# BTN7960_DRIVER_SCH.net
KiCad netlist of a schematic drawn in Altium Designer
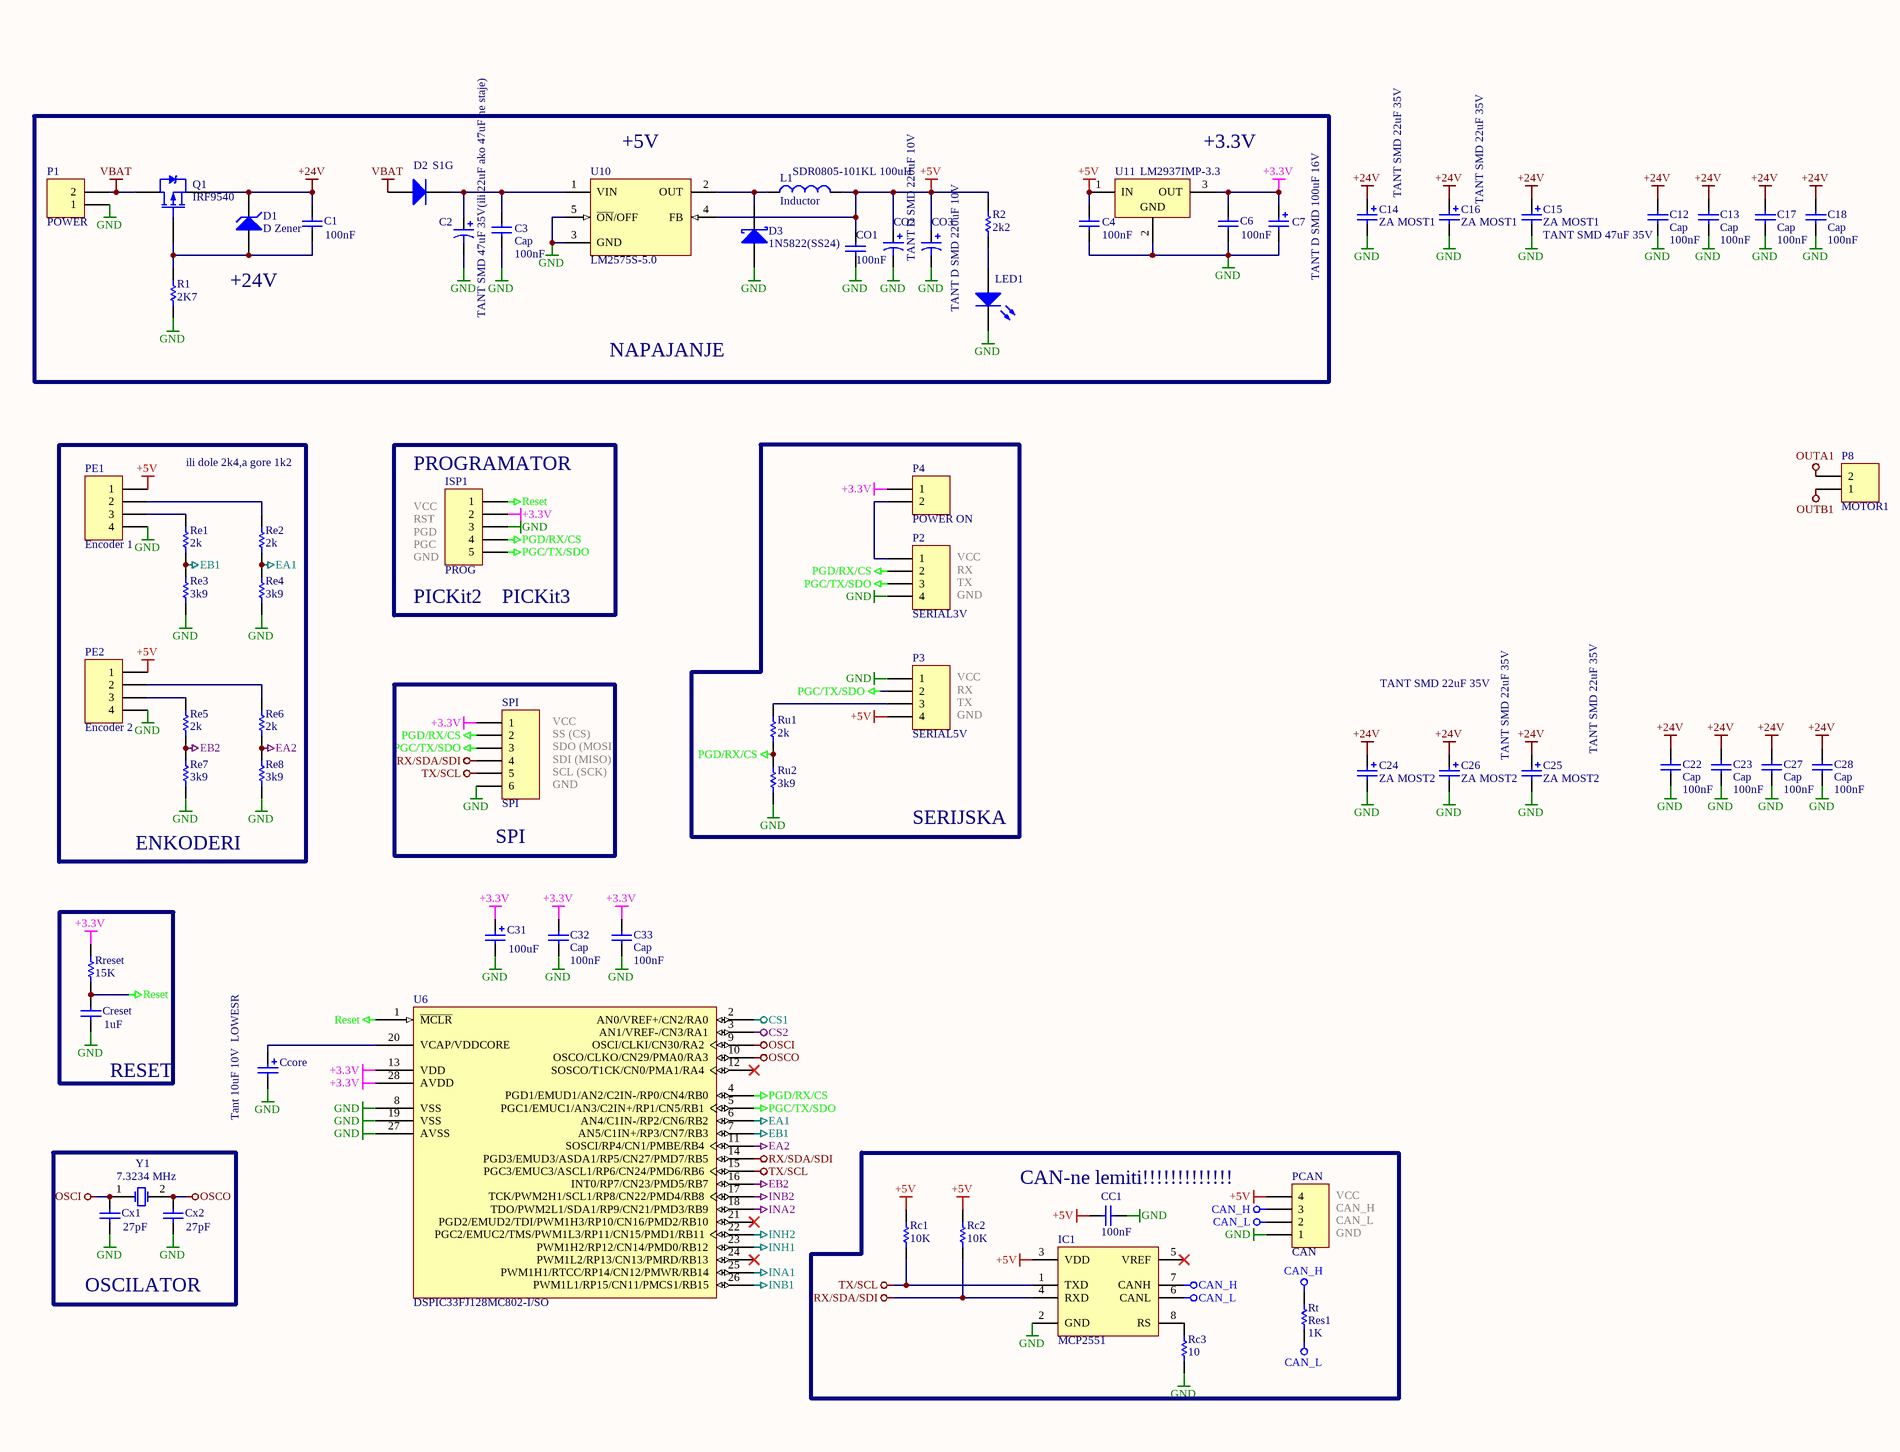
[diagram p0: BTN7960_DRIVER_SCH.SchDoc, left]
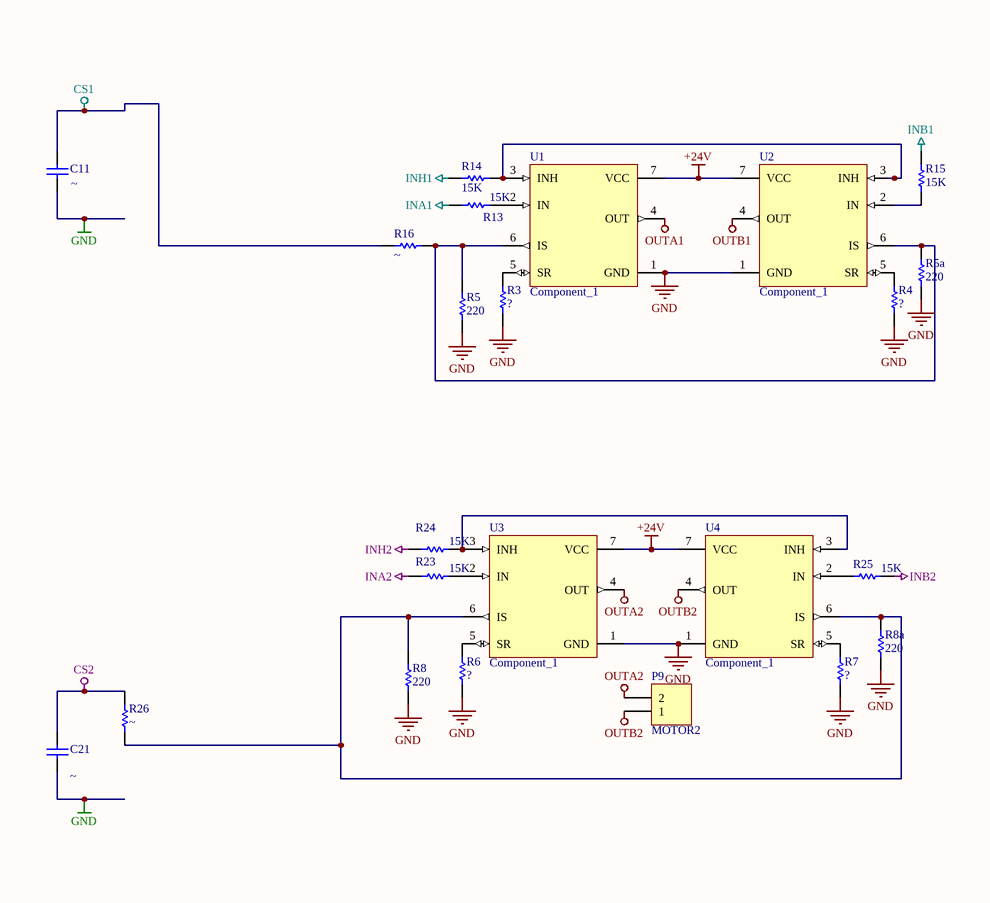
[diagram p1: BTN7960_DRIVER_SCH.SchDoc, right]

(export (version "E")
  (design (tool "Eeschema 10.0.6"))
  (components
    (comp (ref "C1")
      (value "100nF")
      (footprint "1206")
      (description "Capacitor")
      (fields (field (name "Comment") "Cap") (field (name "PUBLISHER") "Altium Limited"))
      (libsource (lib "SCH_LIB") (part "Cap"))
    )
    (comp (ref "C2")
      (value "TANT SMD 47uF 35V(ili 22uF ako 47uF ne staje)")
      (footprint "TC7343-2917")
      (description "Polarized Capacitor (Radial)")
      (fields (field (name "Comment") "Cap Pol1") (field (name "PUBLISHER") "Altium Limited"))
      (libsource (lib "Miscellaneous Devices") (part "Cap Pol1"))
    )
    (comp (ref "C3")
      (value "Cap")
      (footprint "1206")
      (description "Capacitor")
      (fields (field (name "ALTIUM_VALUE") "100nF") (field (name "PUBLISHER") "Altium Limited"))
      (libsource (lib "Miscellaneous Devices") (part "Cap"))
    )
    (comp (ref "C4")
      (value "100nF")
      (footprint "1206")
      (description "Capacitor")
      (fields (field (name "Comment") "Cap") (field (name "PUBLISHER") "Altium Limited"))
      (libsource (lib "SCH_LIB") (part "Cap"))
    )
    (comp (ref "C6")
      (value "100nF")
      (footprint "1206")
      (description "Capacitor")
      (fields (field (name "Comment") "Cap") (field (name "PUBLISHER") "Altium Limited"))
      (libsource (lib "SCH_LIB") (part "Cap"))
    )
    (comp (ref "C7")
      (value "TANT D SMD 100uF 16V")
      (footprint "TC7343-2917")
      (description "Polarized Capacitor (Radial)")
      (fields (field (name "Comment") "ECAP") (field (name "PUBLISHER") "Altium Limited"))
      (libsource (lib "SCH_LIB") (part "Cap Pol1"))
    )
    (comp (ref "C11")
      (value "~")
      (footprint "1206")
      (description "Capacitor")
      (fields (field (name "Comment") "Cap") (field (name "PUBLISHER") "Altium Limited"))
      (libsource (lib "SCH_LIB") (part "Cap"))
    )
    (comp (ref "C12")
      (value "Cap")
      (footprint "1206")
      (description "Capacitor")
      (fields (field (name "ALTIUM_VALUE") "100nF") (field (name "PUBLISHER") "Altium Limited"))
      (libsource (lib "SCH_LIB") (part "Cap"))
    )
    (comp (ref "C13")
      (value "Cap")
      (footprint "1206")
      (description "Capacitor")
      (fields (field (name "ALTIUM_VALUE") "100nF") (field (name "PUBLISHER") "Altium Limited"))
      (libsource (lib "SCH_LIB") (part "Cap"))
    )
    (comp (ref "C14")
      (value "ZA MOST1")
      (footprint "VNH_DRAJVER_PCB_v2.1:TC7343-2917")
      (description "Polarized Capacitor (Radial)")
      (fields (field (name "ALTIUM_VALUE") "TANT SMD 22uF 35V") (field (name "PUBLISHER") "Altium Limited"))
      (libsource (lib "SCH_LIB") (part "Cap Pol1"))
    )
    (comp (ref "C15")
      (value "ZA MOST1")
      (footprint "TC7343-2917")
      (description "Polarized Capacitor (Radial)")
      (fields (field (name "ALTIUM_VALUE") "TANT SMD 47uF 35V") (field (name "PUBLISHER") "Altium Limited"))
      (libsource (lib "SCH_LIB") (part "Cap Pol1"))
    )
    (comp (ref "C16")
      (value "ZA MOST1")
      (footprint "VNH_DRAJVER_PCB_v2.1:TC7343-2917")
      (description "Polarized Capacitor (Radial)")
      (fields (field (name "ALTIUM_VALUE") "TANT SMD 22uF 35V") (field (name "PUBLISHER") "Altium Limited"))
      (libsource (lib "SCH_LIB") (part "Cap Pol1"))
    )
    (comp (ref "C17")
      (value "Cap")
      (footprint "1206")
      (description "Capacitor")
      (fields (field (name "ALTIUM_VALUE") "100nF") (field (name "PUBLISHER") "Altium Limited"))
      (libsource (lib "SCH_LIB") (part "Cap"))
    )
    (comp (ref "C18")
      (value "Cap")
      (footprint "1206")
      (description "Capacitor")
      (fields (field (name "ALTIUM_VALUE") "100nF") (field (name "PUBLISHER") "Altium Limited"))
      (libsource (lib "SCH_LIB") (part "Cap"))
    )
    (comp (ref "C21")
      (value "~")
      (footprint "1206")
      (description "Capacitor")
      (fields (field (name "Comment") "Cap") (field (name "PUBLISHER") "Altium Limited"))
      (libsource (lib "SCH_LIB") (part "Cap"))
    )
    (comp (ref "C22")
      (value "Cap")
      (footprint "1206")
      (description "Capacitor")
      (fields (field (name "ALTIUM_VALUE") "100nF") (field (name "PUBLISHER") "Altium Limited"))
      (libsource (lib "SCH_LIB") (part "Cap"))
    )
    (comp (ref "C23")
      (value "Cap")
      (footprint "1206")
      (description "Capacitor")
      (fields (field (name "ALTIUM_VALUE") "100nF") (field (name "PUBLISHER") "Altium Limited"))
      (libsource (lib "SCH_LIB") (part "Cap"))
    )
    (comp (ref "C24")
      (value "ZA MOST2")
      (footprint "TC7343-2917")
      (description "Polarized Capacitor (Radial)")
      (fields (field (name "ALTIUM_VALUE") "TANT SMD 22uF 35V") (field (name "PUBLISHER") "Altium Limited"))
      (libsource (lib "SCH_LIB") (part "Cap Pol1"))
    )
    (comp (ref "C25")
      (value "ZA MOST2")
      (footprint "TC7343-2917")
      (description "Polarized Capacitor (Radial)")
      (fields (field (name "ALTIUM_VALUE") "TANT SMD 22uF 35V") (field (name "PUBLISHER") "Altium Limited"))
      (libsource (lib "SCH_LIB") (part "Cap Pol1"))
    )
    (comp (ref "C26")
      (value "ZA MOST2")
      (footprint "TC7343-2917")
      (description "Polarized Capacitor (Radial)")
      (fields (field (name "ALTIUM_VALUE") "TANT SMD 22uF 35V") (field (name "PUBLISHER") "Altium Limited"))
      (libsource (lib "SCH_LIB") (part "Cap Pol1"))
    )
    (comp (ref "C27")
      (value "Cap")
      (footprint "1206")
      (description "Capacitor")
      (fields (field (name "ALTIUM_VALUE") "100nF") (field (name "PUBLISHER") "Altium Limited"))
      (libsource (lib "SCH_LIB") (part "Cap"))
    )
    (comp (ref "C28")
      (value "Cap")
      (footprint "1206")
      (description "Capacitor")
      (fields (field (name "ALTIUM_VALUE") "100nF") (field (name "PUBLISHER") "Altium Limited"))
      (libsource (lib "SCH_LIB") (part "Cap"))
    )
    (comp (ref "C31")
      (value "100uF")
      (footprint "TC7343-2917")
      (description "Polarized Capacitor (Radial)")
      (fields (field (name "Comment") "ZA MOST1") (field (name "PUBLISHER") "Altium Limited"))
      (libsource (lib "SCH_LIB") (part "Cap Pol1"))
    )
    (comp (ref "C32")
      (value "Cap")
      (footprint "1206")
      (description "Capacitor")
      (fields (field (name "ALTIUM_VALUE") "100nF") (field (name "PUBLISHER") "Altium Limited"))
      (libsource (lib "SCH_LIB") (part "Cap"))
    )
    (comp (ref "C33")
      (value "Cap")
      (footprint "1206")
      (description "Capacitor")
      (fields (field (name "ALTIUM_VALUE") "100nF") (field (name "PUBLISHER") "Altium Limited"))
      (libsource (lib "SCH_LIB") (part "Cap"))
    )
    (comp (ref "CC1")
      (value "100nF")
      (footprint "1206")
      (description "Capacitor")
      (fields (field (name "Comment") "Cap") (field (name "PUBLISHER") "Altium Limited"))
      (libsource (lib "SCH_LIB") (part "Cap"))
    )
    (comp (ref "Ccore")
      (value "Tant 10uF 10V  LOWESR")
      (footprint "VNH_DRAJVER_PCB_v2.1:TC7343-2917")
      (description "Polarized Capacitor (Radial)")
      (fields (field (name "Comment") "ECAP") (field (name "PUBLISHER") "Altium Limited"))
      (libsource (lib "SCH_LIB") (part "Cap Pol1"))
    )
    (comp (ref "CO1")
      (value "100nF")
      (footprint "1206")
      (description "Capacitor")
      (fields (field (name "Comment") "Cap") (field (name "PUBLISHER") "Altium Limited"))
      (libsource (lib "Miscellaneous Devices") (part "Cap"))
    )
    (comp (ref "CO2")
      (value "TANT D SMD 220uF 10V")
      (footprint "TC7343-2917")
      (description "Polarized Capacitor (Radial)")
      (fields (field (name "Comment") "Cap Pol1") (field (name "PUBLISHER") "Altium Limited"))
      (libsource (lib "Miscellaneous Devices") (part "Cap Pol1"))
    )
    (comp (ref "CO3")
      (value "TANT D SMD 220uF 10V")
      (footprint "TC7343-2917")
      (description "Polarized Capacitor (Radial)")
      (fields (field (name "Comment") "Cap Pol1") (field (name "PUBLISHER") "Altium Limited"))
      (libsource (lib "Miscellaneous Devices") (part "Cap Pol1"))
    )
    (comp (ref "Creset")
      (value "1uF")
      (footprint "1206")
      (description "Capacitor")
      (fields (field (name "Comment") "Cap") (field (name "PUBLISHER") "Altium Limited"))
      (libsource (lib "SCH_LIB") (part "Cap"))
    )
    (comp (ref "Cx1")
      (value "27pF")
      (footprint "1206")
      (description "Capacitor")
      (fields (field (name "Comment") "Cap") (field (name "PUBLISHER") "Altium Limited"))
      (libsource (lib "SCH_LIB") (part "Cap"))
    )
    (comp (ref "Cx2")
      (value "27pF")
      (footprint "1206")
      (description "Capacitor")
      (fields (field (name "Comment") "Cap") (field (name "PUBLISHER") "Altium Limited"))
      (libsource (lib "SCH_LIB") (part "Cap"))
    )
    (comp (ref "D1")
      (value "D Zener")
      (footprint "GLAVNA_LPC21482:DSO-C2/X2.3")
      (description "Zener Diode")
      (fields (field (name "PUBLISHER") "Altium Limited"))
      (libsource (lib "SCH_LIB") (part "D Zener"))
    )
    (comp (ref "D2")
      (value "S1G")
      (footprint "GLAVNA_LPC21482:DSO-C2/X2.3")
      (description "High Conductance Fast Diode")
      (fields (field (name "PUBLISHER") "Altium Limited"))
      (libsource (lib "Miscellaneous Devices") (part "Diode 1N914"))
    )
    (comp (ref "D3")
      (value "1N5822(SS24)")
      (footprint "GLAVNA_LPC21482:DSO-C2/X2.3")
      (description "Schottky Diode")
      (fields (field (name "PUBLISHER") "Altium Limited"))
      (libsource (lib "Miscellaneous Devices") (part "D Schottky"))
    )
    (comp (ref "IC1") (value "MCP2551") (footprint "R-8_N") (libsource (lib "SCH_LIB") (part "MCP2551")))
    (comp (ref "ISP1")
      (value "PROG")
      (footprint "HDR1X5")
      (description "Header, 5-Pin")
      (fields (field (name "PUBLISHER") "Altium Limited"))
      (libsource (lib "SCH_LIB") (part "Header 5"))
    )
    (comp (ref "L1")
      (value "Inductor")
      (footprint "SDR0805")
      (fields (field (name "ALTIUM_VALUE") "SDR0805-101KL 100uH") (field (name "PUBLISHER") "Altium Limited"))
      (libsource (lib "Miscellaneous Devices") (part "Inductor"))
    )
    (comp (ref "LD1")
      (value "LED1")
      (footprint "RAD-0.1")
      (description "Typical RED GaAs LED")
      (fields (field (name "PUBLISHER") "Altium Limited"))
      (libsource (lib "SCH_LIB") (part "LED1"))
    )
    (comp (ref "P1")
      (value "POWER")
      (footprint "kombinacija")
      (description "Header, 2-Pin")
      (fields (field (name "PUBLISHER") "Altium Limited"))
      (libsource (lib "SCH_LIB") (part "Header 2"))
    )
    (comp (ref "P2")
      (value "SERIAL3V")
      (footprint "HDR1X4")
      (description "Header, 4-Pin")
      (fields (field (name "PUBLISHER") "Altium Limited"))
      (libsource (lib "Miscellaneous Connectors") (part "Header 4"))
    )
    (comp (ref "P3")
      (value "SERIAL5V")
      (footprint "BRXCON_4")
      (description "Header, 4-Pin")
      (fields (field (name "PUBLISHER") "Altium Limited"))
      (libsource (lib "") (part "Header 4_1"))
    )
    (comp (ref "P4")
      (value "POWER ON")
      (footprint "HDR1X2")
      (description "Header, 2-Pin")
      (fields (field (name "PUBLISHER") "Altium Limited"))
      (libsource (lib "Miscellaneous Connectors") (part "Header 2"))
    )
    (comp (ref "P8")
      (value "MOTOR1")
      (footprint "kombinacija")
      (description "Header, 2-Pin")
      (fields (field (name "PUBLISHER") "Altium Limited"))
      (libsource (lib "") (part "Header 2_1"))
    )
    (comp (ref "P9")
      (value "MOTOR2")
      (footprint "kombinacija")
      (description "Header, 2-Pin")
      (fields (field (name "PUBLISHER") "Altium Limited"))
      (libsource (lib "") (part "Header 2_1"))
    )
    (comp (ref "PCAN")
      (value "CAN")
      (footprint "BRXCON_4")
      (description "Header, 4-Pin")
      (fields (field (name "PUBLISHER") "Altium Limited"))
      (libsource (lib "") (part "Header 4_2"))
    )
    (comp (ref "PE1")
      (value "Encoder 1")
      (footprint "BRXCON_4")
      (description "Header, 4-Pin")
      (fields (field (name "PUBLISHER") "Altium Limited"))
      (libsource (lib "SCH_LIB") (part "Header 4"))
    )
    (comp (ref "PE2")
      (value "Encoder 2")
      (footprint "BRXCON_4")
      (description "Header, 4-Pin")
      (fields (field (name "PUBLISHER") "Altium Limited"))
      (libsource (lib "SCH_LIB") (part "Header 4"))
    )
    (comp (ref "Q1")
      (value "IRF9540")
      (footprint "D2-PAK")
      (description "HEXFET P-Channel Power MOSFET")
      (fields (field (name "PUBLISHER") "Altium Limited"))
      (libsource (lib "SCH_LIB") (part "IRF9540"))
    )
    (comp (ref "R1")
      (value "2K7")
      (footprint "1206")
      (description "Resistor")
      (fields (field (name "Comment") "res") (field (name "PUBLISHER") "Altium Limited"))
      (libsource (lib "SCH_LIB") (part "Res1"))
    )
    (comp (ref "R2")
      (value "2k2")
      (footprint "1206")
      (description "Resistor")
      (fields (field (name "Comment") "res") (field (name "PUBLISHER") "Altium Limited"))
      (libsource (lib "SCH_LIB") (part "Res1"))
    )
    (comp (ref "R3")
      (value "?")
      (footprint "1206")
      (description "Resistor")
      (fields (field (name "Comment") "res") (field (name "PUBLISHER") "Altium Limited"))
      (libsource (lib "SCH_LIB") (part "Res1"))
    )
    (comp (ref "R4")
      (value "?")
      (footprint "1206")
      (description "Resistor")
      (fields (field (name "Comment") "res") (field (name "PUBLISHER") "Altium Limited"))
      (libsource (lib "SCH_LIB") (part "Res1"))
    )
    (comp (ref "R5")
      (value "220")
      (footprint "1206")
      (description "Resistor")
      (fields (field (name "Comment") "res") (field (name "PUBLISHER") "Altium Limited"))
      (libsource (lib "SCH_LIB") (part "Res1"))
    )
    (comp (ref "R5a")
      (value "220")
      (footprint "1206")
      (description "Resistor")
      (fields (field (name "Comment") "res") (field (name "PUBLISHER") "Altium Limited"))
      (libsource (lib "SCH_LIB") (part "Res1"))
    )
    (comp (ref "R6")
      (value "?")
      (footprint "1206")
      (description "Resistor")
      (fields (field (name "Comment") "res") (field (name "PUBLISHER") "Altium Limited"))
      (libsource (lib "SCH_LIB") (part "Res1"))
    )
    (comp (ref "R7")
      (value "?")
      (footprint "1206")
      (description "Resistor")
      (fields (field (name "Comment") "res") (field (name "PUBLISHER") "Altium Limited"))
      (libsource (lib "SCH_LIB") (part "Res1"))
    )
    (comp (ref "R8")
      (value "220")
      (footprint "1206")
      (description "Resistor")
      (fields (field (name "Comment") "res") (field (name "PUBLISHER") "Altium Limited"))
      (libsource (lib "SCH_LIB") (part "Res1"))
    )
    (comp (ref "R8a")
      (value "220")
      (footprint "1206")
      (description "Resistor")
      (fields (field (name "Comment") "res") (field (name "PUBLISHER") "Altium Limited"))
      (libsource (lib "SCH_LIB") (part "Res1"))
    )
    (comp (ref "R13")
      (value "15K")
      (footprint "1206")
      (description "Resistor")
      (fields (field (name "Comment") "res") (field (name "PUBLISHER") "Altium Limited"))
      (libsource (lib "SCH_LIB") (part "Res1"))
    )
    (comp (ref "R14")
      (value "15K")
      (footprint "1206")
      (description "Resistor")
      (fields (field (name "Comment") "res") (field (name "PUBLISHER") "Altium Limited"))
      (libsource (lib "SCH_LIB") (part "Res1"))
    )
    (comp (ref "R15")
      (value "15K")
      (footprint "1206")
      (description "Resistor")
      (fields (field (name "Comment") "res") (field (name "PUBLISHER") "Altium Limited"))
      (libsource (lib "SCH_LIB") (part "Res1"))
    )
    (comp (ref "R16")
      (value "~")
      (footprint "1206")
      (description "Resistor")
      (fields (field (name "Comment") "res") (field (name "PUBLISHER") "Altium Limited"))
      (libsource (lib "SCH_LIB") (part "Res1"))
    )
    (comp (ref "R23")
      (value "15K")
      (footprint "1206")
      (description "Resistor")
      (fields (field (name "Comment") "res") (field (name "PUBLISHER") "Altium Limited"))
      (libsource (lib "SCH_LIB") (part "Res1"))
    )
    (comp (ref "R24")
      (value "15K")
      (footprint "1206")
      (description "Resistor")
      (fields (field (name "Comment") "res") (field (name "PUBLISHER") "Altium Limited"))
      (libsource (lib "SCH_LIB") (part "Res1"))
    )
    (comp (ref "R25")
      (value "15K")
      (footprint "1206")
      (description "Resistor")
      (fields (field (name "Comment") "res") (field (name "PUBLISHER") "Altium Limited"))
      (libsource (lib "SCH_LIB") (part "Res1"))
    )
    (comp (ref "R26")
      (value "~")
      (footprint "1206")
      (description "Resistor")
      (fields (field (name "Comment") "res") (field (name "PUBLISHER") "Altium Limited"))
      (libsource (lib "SCH_LIB") (part "Res1"))
    )
    (comp (ref "Rc1")
      (value "10K")
      (footprint "1206")
      (description "Resistor")
      (fields (field (name "Comment") "res") (field (name "PUBLISHER") "Altium Limited"))
      (libsource (lib "SCH_LIB") (part "Res1"))
    )
    (comp (ref "Rc2")
      (value "10K")
      (footprint "1206")
      (description "Resistor")
      (fields (field (name "Comment") "res") (field (name "PUBLISHER") "Altium Limited"))
      (libsource (lib "SCH_LIB") (part "Res1"))
    )
    (comp (ref "Rc3")
      (value "10")
      (footprint "1206")
      (description "Resistor")
      (fields (field (name "Comment") "res") (field (name "PUBLISHER") "Altium Limited"))
      (libsource (lib "SCH_LIB") (part "Res1"))
    )
    (comp (ref "Re1")
      (value "2k")
      (footprint "1206")
      (description "Resistor")
      (fields (field (name "Comment") "res") (field (name "PUBLISHER") "Altium Limited"))
      (libsource (lib "SCH_LIB") (part "Res1"))
    )
    (comp (ref "Re2")
      (value "2k")
      (footprint "1206")
      (description "Resistor")
      (fields (field (name "Comment") "res") (field (name "PUBLISHER") "Altium Limited"))
      (libsource (lib "SCH_LIB") (part "Res1"))
    )
    (comp (ref "Re3")
      (value "3k9")
      (footprint "1206")
      (description "Resistor")
      (fields (field (name "Comment") "res") (field (name "PUBLISHER") "Altium Limited"))
      (libsource (lib "SCH_LIB") (part "Res1"))
    )
    (comp (ref "Re4")
      (value "3k9")
      (footprint "1206")
      (description "Resistor")
      (fields (field (name "Comment") "res") (field (name "PUBLISHER") "Altium Limited"))
      (libsource (lib "SCH_LIB") (part "Res1"))
    )
    (comp (ref "Re5")
      (value "2k")
      (footprint "1206")
      (description "Resistor")
      (fields (field (name "Comment") "res") (field (name "PUBLISHER") "Altium Limited"))
      (libsource (lib "SCH_LIB") (part "Res1"))
    )
    (comp (ref "Re6")
      (value "2k")
      (footprint "1206")
      (description "Resistor")
      (fields (field (name "Comment") "res") (field (name "PUBLISHER") "Altium Limited"))
      (libsource (lib "SCH_LIB") (part "Res1"))
    )
    (comp (ref "Re7")
      (value "3k9")
      (footprint "1206")
      (description "Resistor")
      (fields (field (name "Comment") "res") (field (name "PUBLISHER") "Altium Limited"))
      (libsource (lib "SCH_LIB") (part "Res1"))
    )
    (comp (ref "Re8")
      (value "3k9")
      (footprint "1206")
      (description "Resistor")
      (fields (field (name "Comment") "res") (field (name "PUBLISHER") "Altium Limited"))
      (libsource (lib "SCH_LIB") (part "Res1"))
    )
    (comp (ref "Rreset")
      (value "15K")
      (footprint "1206")
      (description "Resistor")
      (fields (field (name "Comment") "res") (field (name "PUBLISHER") "Altium Limited"))
      (libsource (lib "SCH_LIB") (part "Res1"))
    )
    (comp (ref "Rt")
      (value "Res1")
      (footprint "1206")
      (description "Resistor")
      (fields (field (name "ALTIUM_VALUE") "1K") (field (name "PUBLISHER") "Altium Limited"))
      (libsource (lib "Miscellaneous Devices") (part "Res1"))
    )
    (comp (ref "Ru1")
      (value "2k")
      (footprint "1206")
      (description "Resistor")
      (fields (field (name "Comment") "res") (field (name "PUBLISHER") "Altium Limited"))
      (libsource (lib "SCH_LIB") (part "Res1"))
    )
    (comp (ref "Ru2")
      (value "3k9")
      (footprint "1206")
      (description "Resistor")
      (fields (field (name "Comment") "res") (field (name "PUBLISHER") "Altium Limited"))
      (libsource (lib "SCH_LIB") (part "Res1"))
    )
    (comp (ref "SPI")
      (value "SPI")
      (footprint "BRXCON_6")
      (description "Header, 6-Pin")
      (fields (field (name "PUBLISHER") "Altium Limited"))
      (libsource (lib "SCH_LIB") (part "Header 6"))
    )
    (comp (ref "U1")
      (value "Component_1")
      (footprint "to263-7")
      (description "btn7960")
      (libsource (lib "btn7960") (part "Component_1"))
    )
    (comp (ref "U2")
      (value "Component_1")
      (footprint "to263-7")
      (description "btn7960")
      (libsource (lib "") (part "Component_1_1"))
    )
    (comp (ref "U3")
      (value "Component_1")
      (footprint "to263-7")
      (description "btn7960")
      (libsource (lib "btn7960") (part "Component_1"))
    )
    (comp (ref "U4")
      (value "Component_1")
      (footprint "to263-7")
      (description "btn7960")
      (libsource (lib "") (part "Component_1_1"))
    )
    (comp (ref "U6")
      (value "DSPIC33FJ128MC802-I/SO")
      (footprint "SOIC-SO28_N")
      (fields (field (name "PUBLISHER") "Altium Limited"))
      (libsource (lib "SCH_LIB") (part "DSPIC33FJ128MC802-I/SO"))
    )
    (comp (ref "U10")
      (value "LM2575S-5.0")
      (footprint "TO-263(5)")
      (description "SIMPLE SWITCHER 1A Step-Down Voltage Regulator")
      (fields
        (field (name "PARTNUMBER") "LM2575HVT-5.0")
        (field (name "MANUFACTURER") "National Semiconductor")
        (field (name "PUBLISHER") "Altium Limited")
      )
      (libsource (lib "NSC Switcher") (part "LM2575HVT-5.0"))
    )
    (comp (ref "U11")
      (value "LM2937IMP-3.3")
      (footprint "SOT223")
      (description "500 mA Low-Dropout Regulator")
      (fields (field (name "PUBLISHER") "Altium Limited"))
      (libsource (lib "SCH_LIB") (part "LM2937IMP-3.3"))
    )
    (comp (ref "Y1")
      (value "7.3234 MHz")
      (footprint "HC-49U")
      (description "Crystal Oscillator")
      (fields (field (name "PUBLISHER") "Altium Limited"))
      (libsource (lib "SCH_LIB") (part "XTAL"))
    )
  )
  (nets
    (net (code "1") (name "+3.3V") (class "Default")
      (node (ref "C31") (pin "1") (pinfunction "1_1") (pintype "passive"))
      (node (ref "C32") (pin "2") (pinfunction "2_2") (pintype "passive"))
      (node (ref "C33") (pin "2") (pinfunction "2_2") (pintype "passive"))
      (node (ref "C6") (pin "2") (pinfunction "2_2") (pintype "passive"))
      (node (ref "C7") (pin "1") (pinfunction "1_1") (pintype "passive"))
      (node (ref "ISP1") (pin "2") (pinfunction "2_2") (pintype "passive"))
      (node (ref "P4") (pin "1") (pinfunction "1_1") (pintype "passive"))
      (node (ref "Rreset") (pin "1") (pinfunction "1_1") (pintype "passive"))
      (node (ref "SPI") (pin "1") (pinfunction "1_1") (pintype "passive"))
      (node (ref "U11") (pin "3") (pinfunction "OUT_3") (pintype "power_in"))
      (node (ref "U6") (pin "13") (pinfunction "VDD_13") (pintype "power_in"))
      (node (ref "U6") (pin "28") (pinfunction "AVDD_28") (pintype "power_in"))
    )
    (net (code "2") (name "+5V") (class "Default")
      (node (ref "C4") (pin "2") (pinfunction "2_2") (pintype "passive"))
      (node (ref "CC1") (pin "2") (pinfunction "2_2") (pintype "passive"))
      (node (ref "CO1") (pin "2") (pinfunction "2_2") (pintype "passive"))
      (node (ref "CO2") (pin "1") (pinfunction "1_1") (pintype "passive"))
      (node (ref "CO3") (pin "1") (pinfunction "1_1") (pintype "passive"))
      (node (ref "IC1") (pin "3") (pinfunction "VDD_3") (pintype "passive"))
      (node (ref "L1") (pin "2") (pinfunction "2_2") (pintype "passive"))
      (node (ref "P3") (pin "4") (pinfunction "4_4") (pintype "passive"))
      (node (ref "PCAN") (pin "4") (pinfunction "4_4") (pintype "passive"))
      (node (ref "PE1") (pin "1") (pinfunction "1_1") (pintype "passive"))
      (node (ref "PE2") (pin "1") (pinfunction "1_1") (pintype "passive"))
      (node (ref "R2") (pin "2") (pinfunction "2_2") (pintype "passive"))
      (node (ref "Rc1") (pin "1") (pinfunction "1_1") (pintype "passive"))
      (node (ref "Rc2") (pin "1") (pinfunction "1_1") (pintype "passive"))
      (node (ref "U10") (pin "4") (pinfunction "FB_4") (pintype "input"))
      (node (ref "U11") (pin "1") (pinfunction "IN_1") (pintype "power_in"))
    )
    (net (code "3") (name "+24V") (class "Default")
      (node (ref "C1") (pin "2") (pinfunction "2_2") (pintype "passive"))
      (node (ref "C12") (pin "2") (pinfunction "2_2") (pintype "passive"))
      (node (ref "C13") (pin "2") (pinfunction "2_2") (pintype "passive"))
      (node (ref "C14") (pin "1") (pinfunction "1_1") (pintype "passive"))
      (node (ref "C15") (pin "1") (pinfunction "1_1") (pintype "passive"))
      (node (ref "C16") (pin "1") (pinfunction "1_1") (pintype "passive"))
      (node (ref "C17") (pin "2") (pinfunction "2_2") (pintype "passive"))
      (node (ref "C18") (pin "2") (pinfunction "2_2") (pintype "passive"))
      (node (ref "C22") (pin "2") (pinfunction "2_2") (pintype "passive"))
      (node (ref "C23") (pin "2") (pinfunction "2_2") (pintype "passive"))
      (node (ref "C24") (pin "1") (pinfunction "1_1") (pintype "passive"))
      (node (ref "C25") (pin "1") (pinfunction "1_1") (pintype "passive"))
      (node (ref "C26") (pin "1") (pinfunction "1_1") (pintype "passive"))
      (node (ref "C27") (pin "2") (pinfunction "2_2") (pintype "passive"))
      (node (ref "C28") (pin "2") (pinfunction "2_2") (pintype "passive"))
      (node (ref "D1") (pin "2") (pinfunction "K_2") (pintype "passive"))
      (node (ref "Q1") (pin "3") (pinfunction "S_3") (pintype "passive"))
      (node (ref "U1") (pin "7") (pinfunction "VCC_7") (pintype "power_in"))
      (node (ref "U2") (pin "7") (pinfunction "VCC_7") (pintype "power_in"))
      (node (ref "U3") (pin "7") (pinfunction "VCC_7") (pintype "power_in"))
      (node (ref "U4") (pin "7") (pinfunction "VCC_7") (pintype "power_in"))
    )
    (net (code "4") (name "CAN_H") (class "Default")
      (node (ref "IC1") (pin "7") (pinfunction "CANH_7") (pintype "passive"))
      (node (ref "PCAN") (pin "3") (pinfunction "3_3") (pintype "passive"))
      (node (ref "Rt") (pin "2") (pinfunction "2_2") (pintype "passive"))
    )
    (net (code "5") (name "CAN_L") (class "Default")
      (node (ref "IC1") (pin "6") (pinfunction "CANL_6") (pintype "passive"))
      (node (ref "PCAN") (pin "2") (pinfunction "2_2") (pintype "passive"))
      (node (ref "Rt") (pin "1") (pinfunction "1_1") (pintype "passive"))
    )
    (net (code "6") (name "CS1") (class "Default")
      (node (ref "C11") (pin "2") (pinfunction "2_2") (pintype "passive"))
      (node (ref "R16") (pin "1") (pinfunction "1_1") (pintype "passive"))
      (node (ref "U6") (pin "2") (pinfunction "AN0/VREF+/CN2/RA0_2") (pintype "bidirectional"))
    )
    (net (code "7") (name "CS2") (class "Default")
      (node (ref "C21") (pin "2") (pinfunction "2_2") (pintype "passive"))
      (node (ref "R26") (pin "1") (pinfunction "1_1") (pintype "passive"))
      (node (ref "U6") (pin "3") (pinfunction "AN1/VREF-/CN3/RA1_3") (pintype "bidirectional"))
    )
    (net (code "8") (name "EA1") (class "Default")
      (node (ref "Re2") (pin "2") (pinfunction "2_2") (pintype "passive"))
      (node (ref "Re4") (pin "1") (pinfunction "1_1") (pintype "passive"))
      (node (ref "U6") (pin "6") (pinfunction "AN4/C1IN-/RP2/CN6/RB2_6") (pintype "bidirectional"))
    )
    (net (code "9") (name "EA2") (class "Default")
      (node (ref "Re6") (pin "2") (pinfunction "2_2") (pintype "passive"))
      (node (ref "Re8") (pin "1") (pinfunction "1_1") (pintype "passive"))
      (node (ref "U6") (pin "11") (pinfunction "SOSCI/RP4/CN1/PMBE/RB4_11") (pintype "bidirectional"))
    )
    (net (code "10") (name "EB1") (class "Default")
      (node (ref "Re1") (pin "2") (pinfunction "2_2") (pintype "passive"))
      (node (ref "Re3") (pin "1") (pinfunction "1_1") (pintype "passive"))
      (node (ref "U6") (pin "7") (pinfunction "AN5/C1IN+/RP3/CN7/RB3_7") (pintype "bidirectional"))
    )
    (net (code "11") (name "EB2") (class "Default")
      (node (ref "Re5") (pin "2") (pinfunction "2_2") (pintype "passive"))
      (node (ref "Re7") (pin "1") (pinfunction "1_1") (pintype "passive"))
      (node (ref "U6") (pin "16") (pinfunction "INT0/RP7/CN23/PMD5/RB7_16") (pintype "bidirectional"))
    )
    (net (code "12") (name "GND") (class "Default")
      (node (ref "C11") (pin "1") (pinfunction "1_1") (pintype "passive"))
      (node (ref "C12") (pin "1") (pinfunction "1_1") (pintype "passive"))
      (node (ref "C13") (pin "1") (pinfunction "1_1") (pintype "passive"))
      (node (ref "C14") (pin "2") (pinfunction "2_2") (pintype "passive"))
      (node (ref "C15") (pin "2") (pinfunction "2_2") (pintype "passive"))
      (node (ref "C16") (pin "2") (pinfunction "2_2") (pintype "passive"))
      (node (ref "C17") (pin "1") (pinfunction "1_1") (pintype "passive"))
      (node (ref "C18") (pin "1") (pinfunction "1_1") (pintype "passive"))
      (node (ref "C2") (pin "2") (pinfunction "2_2") (pintype "passive"))
      (node (ref "C21") (pin "1") (pinfunction "1_1") (pintype "passive"))
      (node (ref "C22") (pin "1") (pinfunction "1_1") (pintype "passive"))
      (node (ref "C23") (pin "1") (pinfunction "1_1") (pintype "passive"))
      (node (ref "C24") (pin "2") (pinfunction "2_2") (pintype "passive"))
      (node (ref "C25") (pin "2") (pinfunction "2_2") (pintype "passive"))
      (node (ref "C26") (pin "2") (pinfunction "2_2") (pintype "passive"))
      (node (ref "C27") (pin "1") (pinfunction "1_1") (pintype "passive"))
      (node (ref "C28") (pin "1") (pinfunction "1_1") (pintype "passive"))
      (node (ref "C3") (pin "1") (pinfunction "1_1") (pintype "passive"))
      (node (ref "C31") (pin "2") (pinfunction "2_2") (pintype "passive"))
      (node (ref "C32") (pin "1") (pinfunction "1_1") (pintype "passive"))
      (node (ref "C33") (pin "1") (pinfunction "1_1") (pintype "passive"))
      (node (ref "C4") (pin "1") (pinfunction "1_1") (pintype "passive"))
      (node (ref "C6") (pin "1") (pinfunction "1_1") (pintype "passive"))
      (node (ref "C7") (pin "2") (pinfunction "2_2") (pintype "passive"))
      (node (ref "CC1") (pin "1") (pinfunction "1_1") (pintype "passive"))
      (node (ref "CO1") (pin "1") (pinfunction "1_1") (pintype "passive"))
      (node (ref "CO2") (pin "2") (pinfunction "2_2") (pintype "passive"))
      (node (ref "CO3") (pin "2") (pinfunction "2_2") (pintype "passive"))
      (node (ref "Ccore") (pin "2") (pinfunction "2_2") (pintype "passive"))
      (node (ref "Creset") (pin "1") (pinfunction "1_1") (pintype "passive"))
      (node (ref "Cx1") (pin "1") (pinfunction "1_1") (pintype "passive"))
      (node (ref "Cx2") (pin "1") (pinfunction "1_1") (pintype "passive"))
      (node (ref "D3") (pin "1") (pinfunction "A_1") (pintype "passive"))
      (node (ref "IC1") (pin "2") (pinfunction "GND_2") (pintype "passive"))
      (node (ref "ISP1") (pin "3") (pinfunction "3_3") (pintype "passive"))
      (node (ref "LD1") (pin "2") (pinfunction "K_2") (pintype "passive"))
      (node (ref "P1") (pin "1") (pinfunction "1_1") (pintype "passive"))
      (node (ref "P2") (pin "4") (pinfunction "4_4") (pintype "passive"))
      (node (ref "P3") (pin "1") (pinfunction "1_1") (pintype "passive"))
      (node (ref "PCAN") (pin "1") (pinfunction "1_1") (pintype "passive"))
      (node (ref "PE1") (pin "4") (pinfunction "4_4") (pintype "passive"))
      (node (ref "PE2") (pin "4") (pinfunction "4_4") (pintype "passive"))
      (node (ref "R1") (pin "1") (pinfunction "1_1") (pintype "passive"))
      (node (ref "R3") (pin "2") (pinfunction "2_2") (pintype "passive"))
      (node (ref "R4") (pin "2") (pinfunction "2_2") (pintype "passive"))
      (node (ref "R5") (pin "2") (pinfunction "2_2") (pintype "passive"))
      (node (ref "R5a") (pin "2") (pinfunction "2_2") (pintype "passive"))
      (node (ref "R6") (pin "2") (pinfunction "2_2") (pintype "passive"))
      (node (ref "R7") (pin "2") (pinfunction "2_2") (pintype "passive"))
      (node (ref "R8") (pin "2") (pinfunction "2_2") (pintype "passive"))
      (node (ref "R8a") (pin "2") (pinfunction "2_2") (pintype "passive"))
      (node (ref "Rc3") (pin "2") (pinfunction "2_2") (pintype "passive"))
      (node (ref "Re3") (pin "2") (pinfunction "2_2") (pintype "passive"))
      (node (ref "Re4") (pin "2") (pinfunction "2_2") (pintype "passive"))
      (node (ref "Re7") (pin "2") (pinfunction "2_2") (pintype "passive"))
      (node (ref "Re8") (pin "2") (pinfunction "2_2") (pintype "passive"))
      (node (ref "Ru2") (pin "2") (pinfunction "2_2") (pintype "passive"))
      (node (ref "SPI") (pin "6") (pinfunction "6_6") (pintype "passive"))
      (node (ref "U1") (pin "1") (pinfunction "GND_1") (pintype "power_in"))
      (node (ref "U10") (pin "3") (pinfunction "GND_3") (pintype "power_in"))
      (node (ref "U10") (pin "5") (pinfunction "~{ON}/OFF_5") (pintype "input"))
      (node (ref "U11") (pin "2") (pinfunction "GND_2") (pintype "power_in"))
      (node (ref "U2") (pin "1") (pinfunction "GND_1") (pintype "power_in"))
      (node (ref "U3") (pin "1") (pinfunction "GND_1") (pintype "power_in"))
      (node (ref "U4") (pin "1") (pinfunction "GND_1") (pintype "power_in"))
      (node (ref "U6") (pin "19") (pinfunction "VSS_19") (pintype "power_in"))
      (node (ref "U6") (pin "27") (pinfunction "AVSS_27") (pintype "power_in"))
      (node (ref "U6") (pin "8") (pinfunction "VSS_8") (pintype "power_in"))
    )
    (net (code "13") (name "INA1") (class "Default")
      (node (ref "R13") (pin "2") (pinfunction "2_2") (pintype "passive"))
      (node (ref "U6") (pin "25") (pinfunction "PWM1H1/RTCC/RP14/CN12/PMWR/RB14_25") (pintype "bidirectional"))
    )
    (net (code "14") (name "INA2") (class "Default")
      (node (ref "R23") (pin "2") (pinfunction "2_2") (pintype "passive"))
      (node (ref "U6") (pin "18") (pinfunction "TDO/PWM2L1/SDA1/RP9/CN21/PMD3/RB9_18") (pintype "bidirectional"))
    )
    (net (code "15") (name "INB1") (class "Default")
      (node (ref "R15") (pin "1") (pinfunction "1_1") (pintype "passive"))
      (node (ref "U6") (pin "26") (pinfunction "PWM1L1/RP15/CN11/PMCS1/RB15_26") (pintype "bidirectional"))
    )
    (net (code "16") (name "INB2") (class "Default")
      (node (ref "R25") (pin "1") (pinfunction "1_1") (pintype "passive"))
      (node (ref "U6") (pin "17") (pinfunction "TCK/PWM2H1/SCL1/RP8/CN22/PMD4/RB8_17") (pintype "bidirectional"))
    )
    (net (code "17") (name "INH1") (class "Default")
      (node (ref "R14") (pin "1") (pinfunction "1_1") (pintype "passive"))
      (node (ref "U6") (pin "23") (pinfunction "PWM1H2/RP12/CN14/PMD0/RB12_23") (pintype "bidirectional"))
    )
    (net (code "18") (name "INH2") (class "Default")
      (node (ref "R24") (pin "2") (pinfunction "2_2") (pintype "passive"))
      (node (ref "U6") (pin "22") (pinfunction "PGC2/EMUC2/TMS/PWM1L3/RP11/CN15/PMD1/RB11_22") (pintype "bidirectional"))
    )
    (net (code "19") (name "Net-(D1-A)") (class "Default")
      (node (ref "C1") (pin "1") (pinfunction "1_1") (pintype "passive"))
      (node (ref "D1") (pin "1") (pinfunction "A_1") (pintype "passive"))
      (node (ref "Q1") (pin "1") (pinfunction "G_1") (pintype "passive"))
      (node (ref "R1") (pin "2") (pinfunction "2_2") (pintype "passive"))
    )
    (net (code "20") (name "Net-(D2-K)") (class "Default")
      (node (ref "C2") (pin "1") (pinfunction "1_1") (pintype "passive"))
      (node (ref "C3") (pin "2") (pinfunction "2_2") (pintype "passive"))
      (node (ref "D2") (pin "2") (pinfunction "K_2") (pintype "passive"))
      (node (ref "U10") (pin "1") (pinfunction "VIN_1") (pintype "power_in"))
    )
    (net (code "21") (name "Net-(D3-K)") (class "Default")
      (node (ref "D3") (pin "2") (pinfunction "K_2") (pintype "passive"))
      (node (ref "L1") (pin "1") (pinfunction "1_1") (pintype "passive"))
      (node (ref "U10") (pin "2") (pinfunction "OUT_2") (pintype "power_in"))
    )
    (net (code "22") (name "Net-(IC1-RS)") (class "Default")
      (node (ref "IC1") (pin "8") (pinfunction "RS_8") (pintype "passive"))
      (node (ref "Rc3") (pin "1") (pinfunction "1_1") (pintype "passive"))
    )
    (net (code "23") (name "Net-(LD1-A)") (class "Default")
      (node (ref "LD1") (pin "1") (pinfunction "A_1") (pintype "passive"))
      (node (ref "R2") (pin "1") (pinfunction "1_1") (pintype "passive"))
    )
    (net (code "24") (name "Net-(P2-Pad1)") (class "Default")
      (node (ref "P2") (pin "1") (pinfunction "1_1") (pintype "passive"))
      (node (ref "P4") (pin "2") (pinfunction "2_2") (pintype "passive"))
    )
    (net (code "25") (name "Net-(P3-Pad3)") (class "Default")
      (node (ref "P3") (pin "3") (pinfunction "3_3") (pintype "passive"))
      (node (ref "Ru1") (pin "1") (pinfunction "1_1") (pintype "passive"))
    )
    (net (code "26") (name "Net-(PE1-Pad2)") (class "Default")
      (node (ref "PE1") (pin "2") (pinfunction "2_2") (pintype "passive"))
      (node (ref "Re2") (pin "1") (pinfunction "1_1") (pintype "passive"))
    )
    (net (code "27") (name "Net-(PE1-Pad3)") (class "Default")
      (node (ref "PE1") (pin "3") (pinfunction "3_3") (pintype "passive"))
      (node (ref "Re1") (pin "1") (pinfunction "1_1") (pintype "passive"))
    )
    (net (code "28") (name "Net-(PE2-Pad2)") (class "Default")
      (node (ref "PE2") (pin "2") (pinfunction "2_2") (pintype "passive"))
      (node (ref "Re6") (pin "1") (pinfunction "1_1") (pintype "passive"))
    )
    (net (code "29") (name "Net-(PE2-Pad3)") (class "Default")
      (node (ref "PE2") (pin "3") (pinfunction "3_3") (pintype "passive"))
      (node (ref "Re5") (pin "1") (pinfunction "1_1") (pintype "passive"))
    )
    (net (code "30") (name "Net-(U1-IN)") (class "Default")
      (node (ref "R13") (pin "1") (pinfunction "1_1") (pintype "passive"))
      (node (ref "U1") (pin "2") (pinfunction "IN_2") (pintype "input"))
    )
    (net (code "31") (name "Net-(U1-INH)") (class "Default")
      (node (ref "R14") (pin "2") (pinfunction "2_2") (pintype "passive"))
      (node (ref "U1") (pin "3") (pinfunction "INH_3") (pintype "input"))
      (node (ref "U2") (pin "3") (pinfunction "INH_3") (pintype "input"))
    )
    (net (code "32") (name "Net-(U1-IS)") (class "Default")
      (node (ref "R16") (pin "2") (pinfunction "2_2") (pintype "passive"))
      (node (ref "R5") (pin "1") (pinfunction "1_1") (pintype "passive"))
      (node (ref "R5a") (pin "1") (pinfunction "1_1") (pintype "passive"))
      (node (ref "U1") (pin "6") (pinfunction "IS_6") (pintype "output"))
      (node (ref "U2") (pin "6") (pinfunction "IS_6") (pintype "output"))
    )
    (net (code "33") (name "Net-(U1-SR)") (class "Default")
      (node (ref "R3") (pin "1") (pinfunction "1_1") (pintype "passive"))
      (node (ref "U1") (pin "5") (pinfunction "SR_5") (pintype "bidirectional"))
    )
    (net (code "34") (name "Net-(U2-IN)") (class "Default")
      (node (ref "R15") (pin "2") (pinfunction "2_2") (pintype "passive"))
      (node (ref "U2") (pin "2") (pinfunction "IN_2") (pintype "input"))
    )
    (net (code "35") (name "Net-(U2-SR)") (class "Default")
      (node (ref "R4") (pin "1") (pinfunction "1_1") (pintype "passive"))
      (node (ref "U2") (pin "5") (pinfunction "SR_5") (pintype "bidirectional"))
    )
    (net (code "36") (name "Net-(U3-IN)") (class "Default")
      (node (ref "R23") (pin "1") (pinfunction "1_1") (pintype "passive"))
      (node (ref "U3") (pin "2") (pinfunction "IN_2") (pintype "input"))
    )
    (net (code "37") (name "Net-(U3-INH)") (class "Default")
      (node (ref "R24") (pin "1") (pinfunction "1_1") (pintype "passive"))
      (node (ref "U3") (pin "3") (pinfunction "INH_3") (pintype "input"))
      (node (ref "U4") (pin "3") (pinfunction "INH_3") (pintype "input"))
    )
    (net (code "38") (name "Net-(U3-IS)") (class "Default")
      (node (ref "R26") (pin "2") (pinfunction "2_2") (pintype "passive"))
      (node (ref "R8") (pin "1") (pinfunction "1_1") (pintype "passive"))
      (node (ref "R8a") (pin "1") (pinfunction "1_1") (pintype "passive"))
      (node (ref "U3") (pin "6") (pinfunction "IS_6") (pintype "output"))
      (node (ref "U4") (pin "6") (pinfunction "IS_6") (pintype "output"))
    )
    (net (code "39") (name "Net-(U3-SR)") (class "Default")
      (node (ref "R6") (pin "1") (pinfunction "1_1") (pintype "passive"))
      (node (ref "U3") (pin "5") (pinfunction "SR_5") (pintype "bidirectional"))
    )
    (net (code "40") (name "Net-(U4-IN)") (class "Default")
      (node (ref "R25") (pin "2") (pinfunction "2_2") (pintype "passive"))
      (node (ref "U4") (pin "2") (pinfunction "IN_2") (pintype "input"))
    )
    (net (code "41") (name "Net-(U4-SR)") (class "Default")
      (node (ref "R7") (pin "1") (pinfunction "1_1") (pintype "passive"))
      (node (ref "U4") (pin "5") (pinfunction "SR_5") (pintype "bidirectional"))
    )
    (net (code "42") (name "Net-(U6-VCAP{slash}VDDCORE)") (class "Default")
      (node (ref "Ccore") (pin "1") (pinfunction "1_1") (pintype "passive"))
      (node (ref "U6") (pin "20") (pinfunction "VCAP/VDDCORE_20") (pintype "power_in"))
    )
    (net (code "43") (name "OSCI") (class "Default")
      (node (ref "Cx1") (pin "2") (pinfunction "2_2") (pintype "passive"))
      (node (ref "U6") (pin "9") (pinfunction "OSCI/CLKI/CN30/RA2_9") (pintype "bidirectional"))
      (node (ref "Y1") (pin "1") (pinfunction "OSC1_1") (pintype "passive"))
    )
    (net (code "44") (name "OSCO") (class "Default")
      (node (ref "Cx2") (pin "2") (pinfunction "2_2") (pintype "passive"))
      (node (ref "U6") (pin "10") (pinfunction "OSCO/CLKO/CN29/PMA0/RA3_10") (pintype "bidirectional"))
      (node (ref "Y1") (pin "2") (pinfunction "OSC2_2") (pintype "passive"))
    )
    (net (code "45") (name "OUTA1") (class "Default")
      (node (ref "P8") (pin "2") (pinfunction "2_2") (pintype "passive"))
      (node (ref "U1") (pin "4") (pinfunction "OUT_4") (pintype "output"))
    )
    (net (code "46") (name "OUTA2") (class "Default")
      (node (ref "P9") (pin "2") (pinfunction "2_2") (pintype "passive"))
      (node (ref "U3") (pin "4") (pinfunction "OUT_4") (pintype "output"))
    )
    (net (code "47") (name "OUTB1") (class "Default")
      (node (ref "P8") (pin "1") (pinfunction "1_1") (pintype "passive"))
      (node (ref "U2") (pin "4") (pinfunction "OUT_4") (pintype "output"))
    )
    (net (code "48") (name "OUTB2") (class "Default")
      (node (ref "P9") (pin "1") (pinfunction "1_1") (pintype "passive"))
      (node (ref "U4") (pin "4") (pinfunction "OUT_4") (pintype "output"))
    )
    (net (code "49") (name "PGC{slash}TX{slash}SDO") (class "Default")
      (node (ref "ISP1") (pin "5") (pinfunction "5_5") (pintype "passive"))
      (node (ref "P2") (pin "3") (pinfunction "3_3") (pintype "passive"))
      (node (ref "P3") (pin "2") (pinfunction "2_2") (pintype "passive"))
      (node (ref "SPI") (pin "3") (pinfunction "3_3") (pintype "passive"))
      (node (ref "U6") (pin "5") (pinfunction "PGC1/EMUC1/AN3/C2IN+/RP1/CN5/RB1_5") (pintype "bidirectional"))
    )
    (net (code "50") (name "PGD{slash}RX{slash}CS") (class "Default")
      (node (ref "ISP1") (pin "4") (pinfunction "4_4") (pintype "passive"))
      (node (ref "P2") (pin "2") (pinfunction "2_2") (pintype "passive"))
      (node (ref "Ru1") (pin "2") (pinfunction "2_2") (pintype "passive"))
      (node (ref "Ru2") (pin "1") (pinfunction "1_1") (pintype "passive"))
      (node (ref "SPI") (pin "2") (pinfunction "2_2") (pintype "passive"))
      (node (ref "U6") (pin "4") (pinfunction "PGD1/EMUD1/AN2/C2IN-/RP0/CN4/RB0_4") (pintype "bidirectional"))
    )
    (net (code "51") (name "RX{slash}SDA{slash}SDI") (class "Default")
      (node (ref "IC1") (pin "4") (pinfunction "RXD_4") (pintype "passive"))
      (node (ref "Rc2") (pin "2") (pinfunction "2_2") (pintype "passive"))
      (node (ref "SPI") (pin "4") (pinfunction "4_4") (pintype "passive"))
      (node (ref "U6") (pin "14") (pinfunction "PGD3/EMUD3/ASDA1/RP5/CN27/PMD7/RB5_14") (pintype "bidirectional"))
    )
    (net (code "52") (name "Reset") (class "Default")
      (node (ref "Creset") (pin "2") (pinfunction "2_2") (pintype "passive"))
      (node (ref "ISP1") (pin "1") (pinfunction "1_1") (pintype "passive"))
      (node (ref "Rreset") (pin "2") (pinfunction "2_2") (pintype "passive"))
      (node (ref "U6") (pin "1") (pinfunction "~{MCLR}_1") (pintype "input"))
    )
    (net (code "53") (name "TX{slash}SCL") (class "Default")
      (node (ref "IC1") (pin "1") (pinfunction "TXD_1") (pintype "passive"))
      (node (ref "Rc1") (pin "2") (pinfunction "2_2") (pintype "passive"))
      (node (ref "SPI") (pin "5") (pinfunction "5_5") (pintype "passive"))
      (node (ref "U6") (pin "15") (pinfunction "PGC3/EMUC3/ASCL1/RP6/CN24/PMD6/RB6_15") (pintype "bidirectional"))
    )
    (net (code "54") (name "VBAT") (class "Default")
      (node (ref "D2") (pin "1") (pinfunction "A_1") (pintype "passive"))
      (node (ref "P1") (pin "2") (pinfunction "2_2") (pintype "passive"))
      (node (ref "Q1") (pin "2") (pinfunction "D_2") (pintype "passive"))
    )
    (net (code "55") (name "unconnected-(IC1-VREF-Pad5)") (class "Default")
      (node (ref "IC1") (pin "5") (pinfunction "VREF_5") (pintype "passive+no_connect"))
    )
    (net (code "56") (name "unconnected-(U6-PGD2{slash}EMUD2{slash}TDI{slash}PWM1H3{slash}RP10{slash}CN16{slash}PMD2{slash}RB10-Pad21)") (class "Default")
      (node (ref "U6") (pin "21") (pinfunction "PGD2/EMUD2/TDI/PWM1H3/RP10/CN16/PMD2/RB10_21") (pintype "bidirectional+no_connect"))
    )
    (net (code "57") (name "unconnected-(U6-PWM1L2{slash}RP13{slash}CN13{slash}PMRD{slash}RB13-Pad24)") (class "Default")
      (node (ref "U6") (pin "24") (pinfunction "PWM1L2/RP13/CN13/PMRD/RB13_24") (pintype "bidirectional+no_connect"))
    )
    (net (code "58") (name "unconnected-(U6-SOSCO{slash}T1CK{slash}CN0{slash}PMA1{slash}RA4-Pad12)") (class "Default")
      (node (ref "U6") (pin "12") (pinfunction "SOSCO/T1CK/CN0/PMA1/RA4_12") (pintype "bidirectional+no_connect"))
    )
  )
)
